# ATtiny_4585_and_4484_programmer.net
KiCad netlist of a schematic drawn in EAGLE
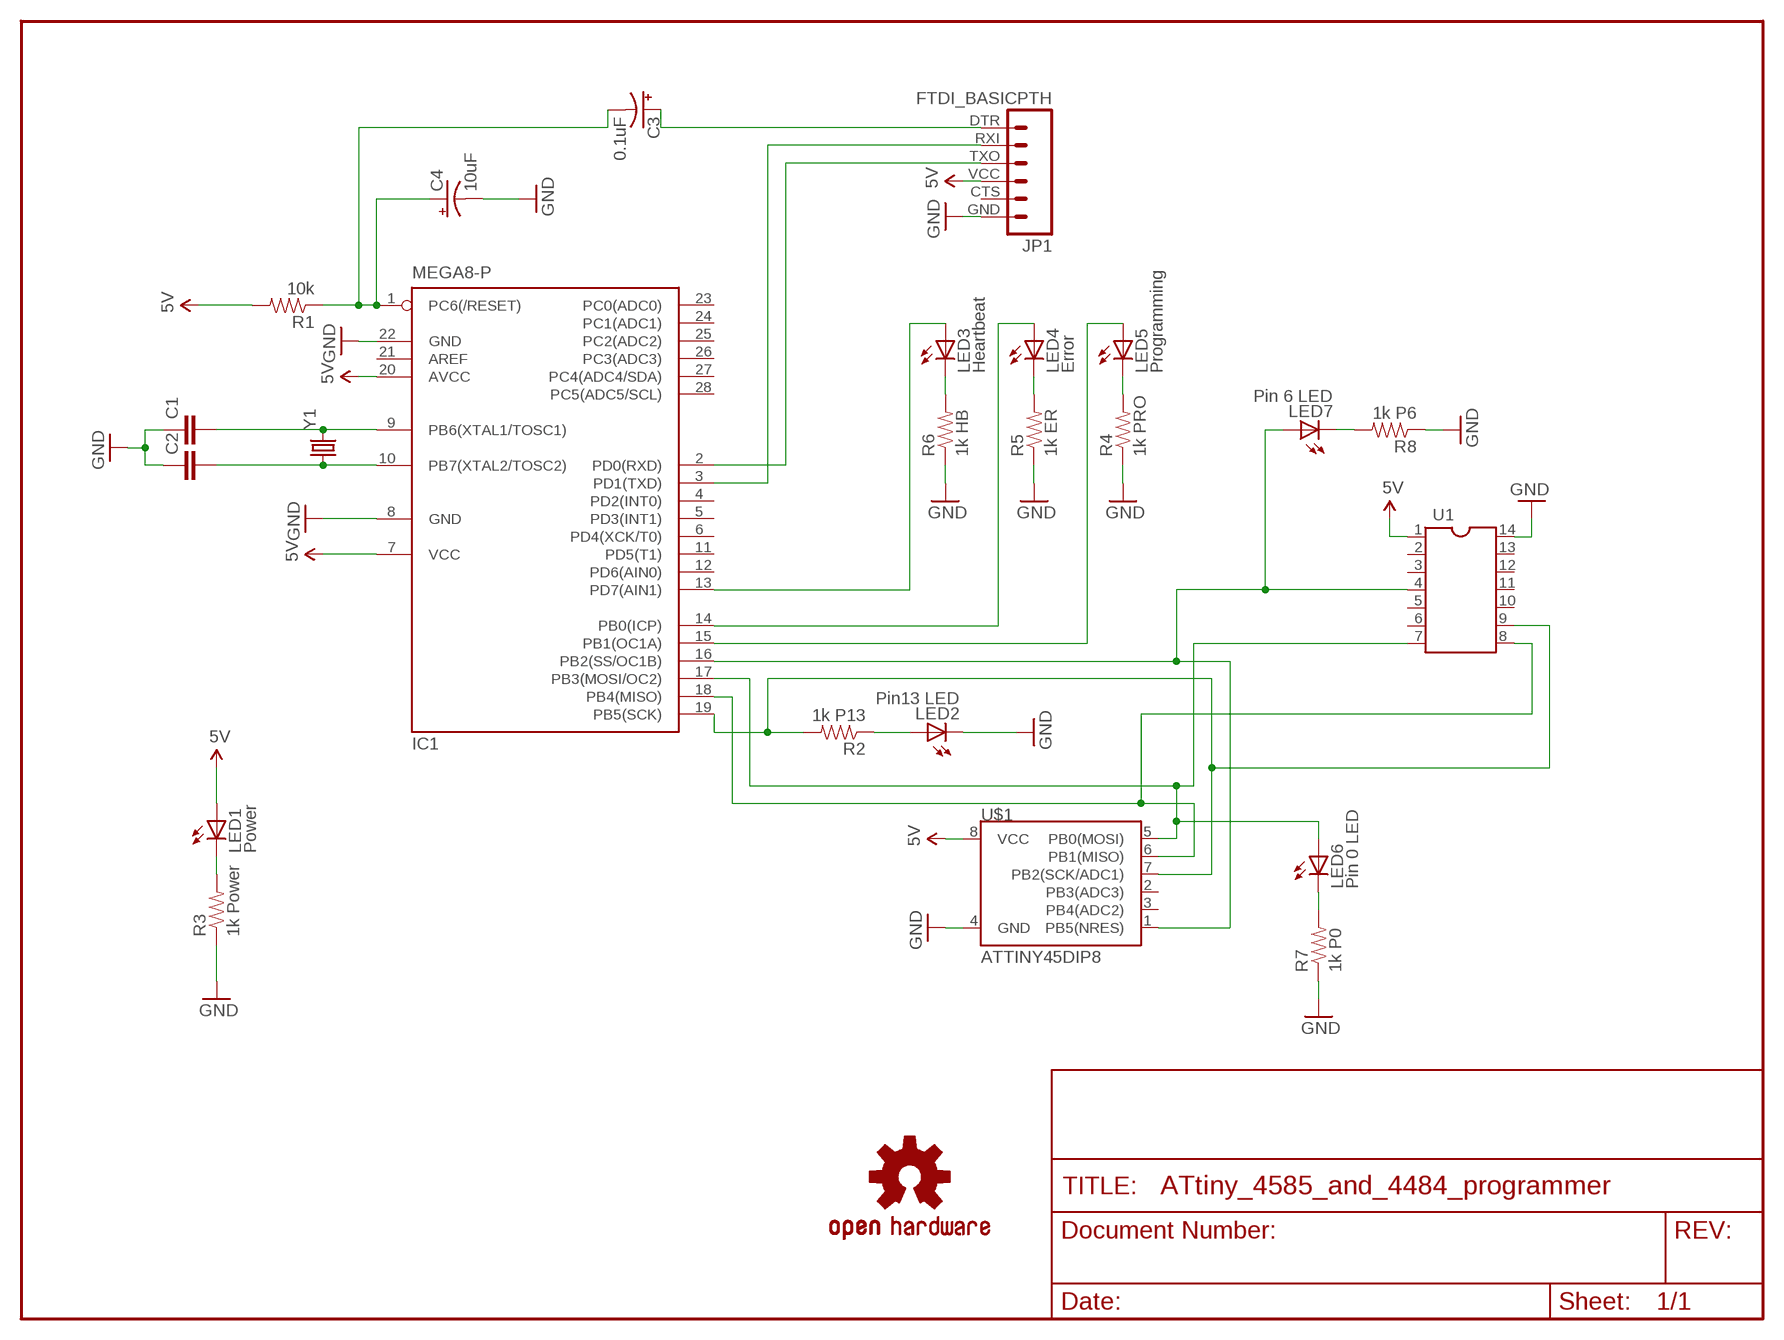
[diagram p0: schematic, sheet 1]

(export (version "E")
  (design (tool "Eeschema 10.0.6"))
  (components
    (comp (ref "C1")
      (value "CAPPTH")
      (footprint "eagle-import:CAP-PTH-SMALL")
      (libsource (lib "eagle-import") (part "CAPPTH"))
    )
    (comp (ref "C2")
      (value "CAPPTH")
      (footprint "eagle-import:CAP-PTH-SMALL")
      (libsource (lib "eagle-import") (part "CAPPTH"))
    )
    (comp (ref "C3")
      (value "0.1uF")
      (footprint "eagle-import:CPOL-RADIAL-10UF-25V")
      (libsource (lib "eagle-import") (part "CAP_POLPTH2"))
    )
    (comp (ref "C4")
      (value "10uF")
      (footprint "eagle-import:CPOL-RADIAL-10UF-25V")
      (libsource (lib "eagle-import") (part "CAP_POLPTH2"))
    )
    (comp (ref "IC1")
      (value "MEGA8-P")
      (footprint "eagle-import:DIL28-3")
      (libsource (lib "eagle-import") (part "MEGA8-P"))
    )
    (comp (ref "JP1")
      (value "FTDI_BASICPTH")
      (footprint "eagle-import:FTDI_BASIC")
      (libsource (lib "eagle-import") (part "FTDI_BASICPTH"))
    )
    (comp (ref "LED1")
      (value "Power")
      (footprint "eagle-import:LED5MM")
      (libsource (lib "eagle-import") (part "LED5MM"))
    )
    (comp (ref "LED2")
      (value "Pin13 LED")
      (footprint "eagle-import:LED5MM")
      (libsource (lib "eagle-import") (part "LED5MM"))
    )
    (comp (ref "LED3")
      (value "Heartbeat")
      (footprint "eagle-import:LED5MM")
      (libsource (lib "eagle-import") (part "LED5MM"))
    )
    (comp (ref "LED4")
      (value "Error")
      (footprint "eagle-import:LED5MM")
      (libsource (lib "eagle-import") (part "LED5MM"))
    )
    (comp (ref "LED5")
      (value "Programming")
      (footprint "eagle-import:LED5MM")
      (libsource (lib "eagle-import") (part "LED5MM"))
    )
    (comp (ref "LED6")
      (value "Pin 0 LED")
      (footprint "eagle-import:LED5MM")
      (libsource (lib "eagle-import") (part "LED5MM"))
    )
    (comp (ref "LED7")
      (value "Pin 6 LED")
      (footprint "eagle-import:LED5MM")
      (libsource (lib "eagle-import") (part "LED5MM"))
    )
    (comp (ref "R1")
      (value "10k")
      (footprint "eagle-import:AXIAL-0.4")
      (libsource (lib "eagle-import") (part "RESISTORPTH-1/4W"))
    )
    (comp (ref "R2")
      (value "1k P13")
      (footprint "eagle-import:AXIAL-0.4")
      (libsource (lib "eagle-import") (part "RESISTORPTH-1/4W"))
    )
    (comp (ref "R3")
      (value "1k Power")
      (footprint "eagle-import:AXIAL-0.4")
      (libsource (lib "eagle-import") (part "RESISTORPTH-1/4W"))
    )
    (comp (ref "R4")
      (value "1k PRO")
      (footprint "eagle-import:AXIAL-0.4")
      (libsource (lib "eagle-import") (part "RESISTORPTH-1/4W"))
    )
    (comp (ref "R5")
      (value "1k ER")
      (footprint "eagle-import:AXIAL-0.4")
      (libsource (lib "eagle-import") (part "RESISTORPTH-1/4W"))
    )
    (comp (ref "R6")
      (value "1k HB")
      (footprint "eagle-import:AXIAL-0.4")
      (libsource (lib "eagle-import") (part "RESISTORPTH-1/4W"))
    )
    (comp (ref "R7")
      (value "1k P0")
      (footprint "eagle-import:AXIAL-0.4")
      (libsource (lib "eagle-import") (part "RESISTORPTH-1/4W"))
    )
    (comp (ref "R8")
      (value "1k P6")
      (footprint "eagle-import:AXIAL-0.4")
      (libsource (lib "eagle-import") (part "RESISTORPTH-1/4W"))
    )
    (comp (ref "U$1")
      (value "ATTINY45DIP8")
      (footprint "eagle-import:DIP08")
      (libsource (lib "eagle-import") (part "ATTINY45DIP8"))
    )
    (comp (ref "U$9")
      (value "OSHW-LOGOM")
      (footprint "eagle-import:OSHW-LOGO-M")
      (libsource (lib "eagle-import") (part "OSHW-LOGOM"))
    )
    (comp (ref "U1")
      (value "DIL14")
      (footprint "eagle-import:DIL14")
      (libsource (lib "eagle-import") (part "DIL14"))
    )
    (comp (ref "Y1")
      (value "CRYSTALHC49US")
      (footprint "eagle-import:HC49US")
      (libsource (lib "eagle-import") (part "CRYSTALHC49US"))
    )
  )
  (nets
    (net (code "1") (name "5V") (class "Default")
      (node (ref "IC1") (pin "20") (pinfunction "AVCC_20") (pintype "power_in"))
      (node (ref "IC1") (pin "7") (pinfunction "VCC_7") (pintype "power_in"))
      (node (ref "JP1") (pin "VCC") (pinfunction "4_VCC") (pintype "passive"))
      (node (ref "LED1") (pin "A") (pinfunction "A_A") (pintype "passive"))
      (node (ref "R1") (pin "P$2") (pinfunction "2_P$2") (pintype "passive"))
      (node (ref "U$1") (pin "8") (pinfunction "VCC_8") (pintype "bidirectional"))
      (node (ref "U1") (pin "1") (pinfunction "1_1") (pintype "passive"))
    )
    (net (code "2") (name "GND") (class "Default")
      (node (ref "C1") (pin "1") (pinfunction "1_1") (pintype "passive"))
      (node (ref "C2") (pin "1") (pinfunction "1_1") (pintype "passive"))
      (node (ref "C4") (pin "2") (pinfunction "-_2") (pintype "passive"))
      (node (ref "IC1") (pin "22") (pinfunction "GND_22") (pintype "power_in"))
      (node (ref "IC1") (pin "8") (pinfunction "GND_8") (pintype "power_in"))
      (node (ref "JP1") (pin "GND") (pinfunction "6_GND") (pintype "passive"))
      (node (ref "LED2") (pin "K") (pinfunction "C_K") (pintype "passive"))
      (node (ref "R3") (pin "P$1") (pinfunction "1_P$1") (pintype "passive"))
      (node (ref "R4") (pin "P$1") (pinfunction "1_P$1") (pintype "passive"))
      (node (ref "R5") (pin "P$1") (pinfunction "1_P$1") (pintype "passive"))
      (node (ref "R6") (pin "P$1") (pinfunction "1_P$1") (pintype "passive"))
      (node (ref "R7") (pin "P$1") (pinfunction "1_P$1") (pintype "passive"))
      (node (ref "R8") (pin "P$1") (pinfunction "1_P$1") (pintype "passive"))
      (node (ref "U$1") (pin "4") (pinfunction "GND_4") (pintype "bidirectional"))
      (node (ref "U1") (pin "14") (pinfunction "14_14") (pintype "passive"))
    )
    (net (code "3") (name "Net-(C3-+)") (class "Default")
      (node (ref "C3") (pin "1") (pinfunction "+_1") (pintype "passive"))
      (node (ref "JP1") (pin "DTR") (pinfunction "1_DTR") (pintype "passive"))
    )
    (net (code "4") (name "Net-(C3--)") (class "Default")
      (node (ref "C3") (pin "2") (pinfunction "-_2") (pintype "passive"))
      (node (ref "C4") (pin "1") (pinfunction "+_1") (pintype "passive"))
      (node (ref "IC1") (pin "1") (pinfunction "PC6(/RESET)_1") (pintype "bidirectional"))
      (node (ref "R1") (pin "P$1") (pinfunction "1_P$1") (pintype "passive"))
    )
    (net (code "5") (name "Net-(IC1-PB0(ICP))") (class "Default")
      (node (ref "IC1") (pin "14") (pinfunction "PB0(ICP)_14") (pintype "bidirectional"))
      (node (ref "LED4") (pin "A") (pinfunction "A_A") (pintype "passive"))
    )
    (net (code "6") (name "Net-(IC1-PB1(OC1A))") (class "Default")
      (node (ref "IC1") (pin "15") (pinfunction "PB1(OC1A)_15") (pintype "bidirectional"))
      (node (ref "LED5") (pin "A") (pinfunction "A_A") (pintype "passive"))
    )
    (net (code "7") (name "Net-(IC1-PB2(SS{slash}OC1B))") (class "Default")
      (node (ref "IC1") (pin "16") (pinfunction "PB2(SS/OC1B)_16") (pintype "bidirectional"))
      (node (ref "LED7") (pin "A") (pinfunction "A_A") (pintype "passive"))
      (node (ref "U$1") (pin "1") (pinfunction "PB5(NRES)_1") (pintype "bidirectional"))
      (node (ref "U1") (pin "4") (pinfunction "4_4") (pintype "passive"))
    )
    (net (code "8") (name "Net-(IC1-PB3(MOSI{slash}OC2))") (class "Default")
      (node (ref "IC1") (pin "17") (pinfunction "PB3(MOSI/OC2)_17") (pintype "bidirectional"))
      (node (ref "LED6") (pin "A") (pinfunction "A_A") (pintype "passive"))
      (node (ref "U$1") (pin "5") (pinfunction "PB0(MOSI)_5") (pintype "bidirectional"))
      (node (ref "U1") (pin "7") (pinfunction "7_7") (pintype "passive"))
    )
    (net (code "9") (name "Net-(IC1-PB4(MISO))") (class "Default")
      (node (ref "IC1") (pin "18") (pinfunction "PB4(MISO)_18") (pintype "bidirectional"))
      (node (ref "U$1") (pin "6") (pinfunction "PB1(MISO)_6") (pintype "bidirectional"))
      (node (ref "U1") (pin "8") (pinfunction "8_8") (pintype "passive"))
    )
    (net (code "10") (name "Net-(IC1-PB5(SCK))") (class "Default")
      (node (ref "IC1") (pin "19") (pinfunction "PB5(SCK)_19") (pintype "bidirectional"))
      (node (ref "R2") (pin "P$2") (pinfunction "2_P$2") (pintype "passive"))
      (node (ref "U$1") (pin "7") (pinfunction "PB2(SCK/ADC1)_7") (pintype "bidirectional"))
      (node (ref "U1") (pin "9") (pinfunction "9_9") (pintype "passive"))
    )
    (net (code "11") (name "Net-(IC1-PB6(XTAL1{slash}TOSC1))") (class "Default")
      (node (ref "C1") (pin "2") (pinfunction "2_2") (pintype "passive"))
      (node (ref "IC1") (pin "9") (pinfunction "PB6(XTAL1/TOSC1)_9") (pintype "bidirectional"))
      (node (ref "Y1") (pin "2") (pinfunction "2_2") (pintype "passive"))
    )
    (net (code "12") (name "Net-(IC1-PB7(XTAL2{slash}TOSC2))") (class "Default")
      (node (ref "C2") (pin "2") (pinfunction "2_2") (pintype "passive"))
      (node (ref "IC1") (pin "10") (pinfunction "PB7(XTAL2/TOSC2)_10") (pintype "bidirectional"))
      (node (ref "Y1") (pin "1") (pinfunction "1_1") (pintype "passive"))
    )
    (net (code "13") (name "Net-(IC1-PD0(RXD))") (class "Default")
      (node (ref "IC1") (pin "2") (pinfunction "PD0(RXD)_2") (pintype "bidirectional"))
      (node (ref "JP1") (pin "TXO") (pinfunction "3_TXO") (pintype "passive"))
    )
    (net (code "14") (name "Net-(IC1-PD1(TXD))") (class "Default")
      (node (ref "IC1") (pin "3") (pinfunction "PD1(TXD)_3") (pintype "bidirectional"))
      (node (ref "JP1") (pin "RXI") (pinfunction "2_RXI") (pintype "passive"))
    )
    (net (code "15") (name "Net-(IC1-PD7(AIN1))") (class "Default")
      (node (ref "IC1") (pin "13") (pinfunction "PD7(AIN1)_13") (pintype "bidirectional"))
      (node (ref "LED3") (pin "A") (pinfunction "A_A") (pintype "passive"))
    )
    (net (code "16") (name "Net-(LED1-C)") (class "Default")
      (node (ref "LED1") (pin "K") (pinfunction "C_K") (pintype "passive"))
      (node (ref "R3") (pin "P$2") (pinfunction "2_P$2") (pintype "passive"))
    )
    (net (code "17") (name "Net-(LED3-C)") (class "Default")
      (node (ref "LED3") (pin "K") (pinfunction "C_K") (pintype "passive"))
      (node (ref "R6") (pin "P$2") (pinfunction "2_P$2") (pintype "passive"))
    )
    (net (code "18") (name "Net-(LED4-C)") (class "Default")
      (node (ref "LED4") (pin "K") (pinfunction "C_K") (pintype "passive"))
      (node (ref "R5") (pin "P$2") (pinfunction "2_P$2") (pintype "passive"))
    )
    (net (code "19") (name "Net-(LED5-C)") (class "Default")
      (node (ref "LED5") (pin "K") (pinfunction "C_K") (pintype "passive"))
      (node (ref "R4") (pin "P$2") (pinfunction "2_P$2") (pintype "passive"))
    )
    (net (code "20") (name "Net-(LED6-C)") (class "Default")
      (node (ref "LED6") (pin "K") (pinfunction "C_K") (pintype "passive"))
      (node (ref "R7") (pin "P$2") (pinfunction "2_P$2") (pintype "passive"))
    )
    (net (code "21") (name "Net-(LED7-C)") (class "Default")
      (node (ref "LED7") (pin "K") (pinfunction "C_K") (pintype "passive"))
      (node (ref "R8") (pin "P$2") (pinfunction "2_P$2") (pintype "passive"))
    )
    (net (code "22") (name "Net-(R2-1)") (class "Default")
      (node (ref "LED2") (pin "A") (pinfunction "A_A") (pintype "passive"))
      (node (ref "R2") (pin "P$1") (pinfunction "1_P$1") (pintype "passive"))
    )
    (net (code "23") (name "unconnected-(IC1-AREF-Pad21)") (class "Default")
      (node (ref "IC1") (pin "21") (pinfunction "AREF_21") (pintype "passive"))
    )
    (net (code "24") (name "unconnected-(IC1-PC0(ADC0)-Pad23)") (class "Default")
      (node (ref "IC1") (pin "23") (pinfunction "PC0(ADC0)_23") (pintype "bidirectional"))
    )
    (net (code "25") (name "unconnected-(IC1-PC1(ADC1)-Pad24)") (class "Default")
      (node (ref "IC1") (pin "24") (pinfunction "PC1(ADC1)_24") (pintype "bidirectional"))
    )
    (net (code "26") (name "unconnected-(IC1-PC2(ADC2)-Pad25)") (class "Default")
      (node (ref "IC1") (pin "25") (pinfunction "PC2(ADC2)_25") (pintype "bidirectional"))
    )
    (net (code "27") (name "unconnected-(IC1-PC3(ADC3)-Pad26)") (class "Default")
      (node (ref "IC1") (pin "26") (pinfunction "PC3(ADC3)_26") (pintype "bidirectional"))
    )
    (net (code "28") (name "unconnected-(IC1-PC4(ADC4{slash}SDA)-Pad27)") (class "Default")
      (node (ref "IC1") (pin "27") (pinfunction "PC4(ADC4/SDA)_27") (pintype "bidirectional"))
    )
    (net (code "29") (name "unconnected-(IC1-PC5(ADC5{slash}SCL)-Pad28)") (class "Default")
      (node (ref "IC1") (pin "28") (pinfunction "PC5(ADC5/SCL)_28") (pintype "bidirectional"))
    )
    (net (code "30") (name "unconnected-(IC1-PD2(INT0)-Pad4)") (class "Default")
      (node (ref "IC1") (pin "4") (pinfunction "PD2(INT0)_4") (pintype "bidirectional"))
    )
    (net (code "31") (name "unconnected-(IC1-PD3(INT1)-Pad5)") (class "Default")
      (node (ref "IC1") (pin "5") (pinfunction "PD3(INT1)_5") (pintype "bidirectional"))
    )
    (net (code "32") (name "unconnected-(IC1-PD4(XCK{slash}T0)-Pad6)") (class "Default")
      (node (ref "IC1") (pin "6") (pinfunction "PD4(XCK/T0)_6") (pintype "bidirectional"))
    )
    (net (code "33") (name "unconnected-(IC1-PD5(T1)-Pad11)") (class "Default")
      (node (ref "IC1") (pin "11") (pinfunction "PD5(T1)_11") (pintype "bidirectional"))
    )
    (net (code "34") (name "unconnected-(IC1-PD6(AIN0)-Pad12)") (class "Default")
      (node (ref "IC1") (pin "12") (pinfunction "PD6(AIN0)_12") (pintype "bidirectional"))
    )
    (net (code "35") (name "unconnected-(JP1-5-PadCTS)") (class "Default")
      (node (ref "JP1") (pin "CTS") (pinfunction "5_CTS") (pintype "passive"))
    )
    (net (code "36") (name "unconnected-(U$1-PB3(ADC3)-Pad2)") (class "Default")
      (node (ref "U$1") (pin "2") (pinfunction "PB3(ADC3)_2") (pintype "bidirectional"))
    )
    (net (code "37") (name "unconnected-(U$1-PB4(ADC2)-Pad3)") (class "Default")
      (node (ref "U$1") (pin "3") (pinfunction "PB4(ADC2)_3") (pintype "bidirectional"))
    )
    (net (code "38") (name "unconnected-(U1-Pad2)") (class "Default")
      (node (ref "U1") (pin "2") (pinfunction "2_2") (pintype "passive"))
    )
    (net (code "39") (name "unconnected-(U1-Pad3)") (class "Default")
      (node (ref "U1") (pin "3") (pinfunction "3_3") (pintype "passive"))
    )
    (net (code "40") (name "unconnected-(U1-Pad5)") (class "Default")
      (node (ref "U1") (pin "5") (pinfunction "5_5") (pintype "passive"))
    )
    (net (code "41") (name "unconnected-(U1-Pad6)") (class "Default")
      (node (ref "U1") (pin "6") (pinfunction "6_6") (pintype "passive"))
    )
    (net (code "42") (name "unconnected-(U1-Pad10)") (class "Default")
      (node (ref "U1") (pin "10") (pinfunction "10_10") (pintype "passive"))
    )
    (net (code "43") (name "unconnected-(U1-Pad11)") (class "Default")
      (node (ref "U1") (pin "11") (pinfunction "11_11") (pintype "passive"))
    )
    (net (code "44") (name "unconnected-(U1-Pad12)") (class "Default")
      (node (ref "U1") (pin "12") (pinfunction "12_12") (pintype "passive"))
    )
    (net (code "45") (name "unconnected-(U1-Pad13)") (class "Default")
      (node (ref "U1") (pin "13") (pinfunction "13_13") (pintype "passive"))
    )
  )
)
